# PSU.net
KiCad netlist of a schematic drawn in Altium Designer
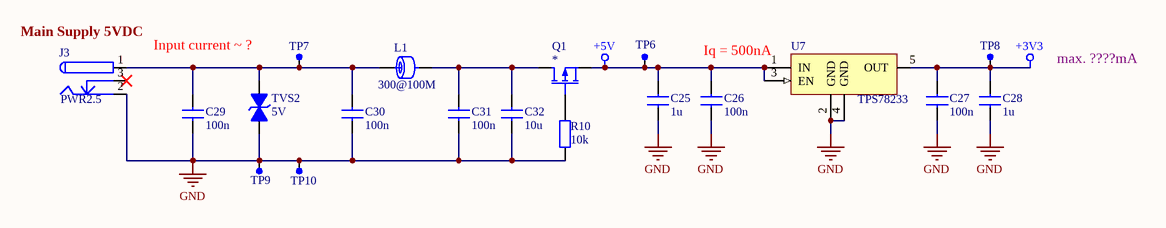
[diagram p0: PSU.SchDoc]

(export (version "E")
  (design (tool "Eeschema 10.0.6"))
  (components
    (comp (ref "C25")
      (value "1u")
      (footprint "C_0805")
      (description "Capacitor")
      (libsource (lib "passive") (part "Capacitor"))
    )
    (comp (ref "C26")
      (value "100n")
      (footprint "C_0805")
      (description "Capacitor")
      (libsource (lib "passive") (part "Capacitor"))
    )
    (comp (ref "C27")
      (value "100n")
      (footprint "C_0805")
      (description "Capacitor")
      (libsource (lib "passive") (part "Capacitor"))
    )
    (comp (ref "C28")
      (value "1u")
      (footprint "C_0805")
      (description "Capacitor")
      (libsource (lib "passive") (part "Capacitor"))
    )
    (comp (ref "C29")
      (value "100n")
      (footprint "C_0805")
      (description "Capacitor")
      (libsource (lib "passive") (part "Capacitor"))
    )
    (comp (ref "C30")
      (value "100n")
      (footprint "C_0805")
      (description "Capacitor")
      (libsource (lib "passive") (part "Capacitor"))
    )
    (comp (ref "C31")
      (value "100n")
      (footprint "C_0805")
      (description "Capacitor")
      (libsource (lib "passive") (part "Capacitor"))
    )
    (comp (ref "C32")
      (value "10u")
      (footprint "C_0805")
      (description "Capacitor")
      (libsource (lib "passive") (part "Capacitor"))
    )
    (comp (ref "J3")
      (value "PWR2.5")
      (footprint "WE_WR_DC_694106301002")
      (description "Low Voltage Power Supply Connector")
      (libsource (lib "boxer_mechanical") (part "PWR2.5"))
    )
    (comp (ref "L1")
      (value "300@100M")
      (footprint "L_0805")
      (description "Ferrite Bead")
      (fields (field (name "Comment") "742792031"))
      (libsource (lib "passive") (part "FB"))
    )
    (comp (ref "Q1")
      (value "MOSFET-P")
      (footprint "SOT-23")
      (description "P-Channel MOSFET")
      (fields (field (name "ALTIUM_VALUE") "*"))
      (libsource (lib "passive") (part "MOSFET-P"))
    )
    (comp (ref "R10")
      (value "10k")
      (footprint "R_0805")
      (description "Resistor")
      (libsource (lib "passive") (part "Resistor"))
    )
    (comp (ref "TP6")
      (value "TEST PAD")
      (footprint "PIN")
      (description "PAD 1.5mm")
      (libsource (lib "mechanical") (part "TEST_PAD"))
    )
    (comp (ref "TP7")
      (value "TEST PAD")
      (footprint "PIN")
      (description "PAD 1.5mm")
      (libsource (lib "boxer_mechanical") (part "TEST_PAD"))
    )
    (comp (ref "TP8")
      (value "TEST PAD")
      (footprint "PIN")
      (description "PAD 1.5mm")
      (libsource (lib "mechanical") (part "TEST_PAD"))
    )
    (comp (ref "TP9")
      (value "TEST PAD")
      (footprint "PIN")
      (description "PAD 1.5mm")
      (libsource (lib "boxer_mechanical") (part "TEST_PAD"))
    )
    (comp (ref "TP10")
      (value "TEST PAD")
      (footprint "PIN")
      (description "PAD 1.5mm")
      (libsource (lib "boxer_mechanical") (part "TEST_PAD"))
    )
    (comp (ref "TVS2")
      (value "5V")
      (footprint "D_1206")
      (description "Transil")
      (fields (field (name "Comment") "SMAJ5.0ALFCT-ND"))
      (libsource (lib "passive") (part "Transil"))
    )
    (comp (ref "U7")
      (value "TPS78233")
      (footprint "SOP5(6)")
      (description "150-mA, ultra-low quiescent qurrent (500 nA) low-dropout linear regulator")
      (libsource (lib "digital") (part "TPS78233"))
    )
  )
  (nets
    (net (code "1") (name "+3V3") (class "Default")
      (node (ref "C27") (pin "1") (pinfunction "1_1") (pintype "passive"))
      (node (ref "C28") (pin "1") (pinfunction "1_1") (pintype "passive"))
      (node (ref "TP8") (pin "1") (pinfunction "1_1") (pintype "passive"))
      (node (ref "U7") (pin "5") (pinfunction "OUT_5") (pintype "power_in"))
    )
    (net (code "2") (name "+5V") (class "Default")
      (node (ref "C25") (pin "1") (pinfunction "1_1") (pintype "passive"))
      (node (ref "C26") (pin "1") (pinfunction "1_1") (pintype "passive"))
      (node (ref "Q1") (pin "2") (pinfunction "S_2") (pintype "passive"))
      (node (ref "TP6") (pin "1") (pinfunction "1_1") (pintype "passive"))
      (node (ref "U7") (pin "1") (pinfunction "IN_1") (pintype "power_in"))
      (node (ref "U7") (pin "3") (pinfunction "EN_3") (pintype "input"))
    )
    (net (code "3") (name "GND") (class "Default")
      (node (ref "C25") (pin "2") (pinfunction "2_2") (pintype "passive"))
      (node (ref "C26") (pin "2") (pinfunction "2_2") (pintype "passive"))
      (node (ref "C27") (pin "2") (pinfunction "2_2") (pintype "passive"))
      (node (ref "C28") (pin "2") (pinfunction "2_2") (pintype "passive"))
      (node (ref "C29") (pin "2") (pinfunction "2_2") (pintype "passive"))
      (node (ref "C30") (pin "2") (pinfunction "2_2") (pintype "passive"))
      (node (ref "C31") (pin "2") (pinfunction "2_2") (pintype "passive"))
      (node (ref "C32") (pin "2") (pinfunction "2_2") (pintype "passive"))
      (node (ref "J3") (pin "2") (pinfunction "2_2") (pintype "power_in"))
      (node (ref "R10") (pin "1") (pinfunction "1_1") (pintype "passive"))
      (node (ref "TP10") (pin "1") (pinfunction "1_1") (pintype "passive"))
      (node (ref "TP9") (pin "1") (pinfunction "1_1") (pintype "passive"))
      (node (ref "TVS2") (pin "1") (pinfunction "A_1") (pintype "passive"))
      (node (ref "U7") (pin "2") (pinfunction "GND_2") (pintype "power_in"))
      (node (ref "U7") (pin "4") (pinfunction "GND_4") (pintype "power_in"))
    )
    (net (code "4") (name "Net-(Q1-D)") (class "Default")
      (node (ref "C31") (pin "1") (pinfunction "1_1") (pintype "passive"))
      (node (ref "C32") (pin "1") (pinfunction "1_1") (pintype "passive"))
      (node (ref "L1") (pin "2") (pinfunction "2_2") (pintype "passive"))
      (node (ref "Q1") (pin "3") (pinfunction "D_3") (pintype "passive"))
    )
    (net (code "5") (name "Net-(Q1-G)") (class "Default")
      (node (ref "Q1") (pin "1") (pinfunction "G_1") (pintype "passive"))
      (node (ref "R10") (pin "2") (pinfunction "2_2") (pintype "passive"))
    )
    (net (code "6") (name "Net-(TVS2-K)") (class "Default")
      (node (ref "C29") (pin "1") (pinfunction "1_1") (pintype "passive"))
      (node (ref "C30") (pin "1") (pinfunction "1_1") (pintype "passive"))
      (node (ref "J3") (pin "1") (pinfunction "1_1") (pintype "power_in"))
      (node (ref "L1") (pin "1") (pinfunction "1_1") (pintype "passive"))
      (node (ref "TP7") (pin "1") (pinfunction "1_1") (pintype "passive"))
      (node (ref "TVS2") (pin "2") (pinfunction "K_2") (pintype "passive"))
    )
    (net (code "7") (name "unconnected-(J3-Pad3)") (class "Default")
      (node (ref "J3") (pin "3") (pinfunction "3_3") (pintype "power_in+no_connect"))
    )
  )
)
